# 1KB_I2C_EEPROM.net
KiCad netlist of a schematic drawn in Altium Designer
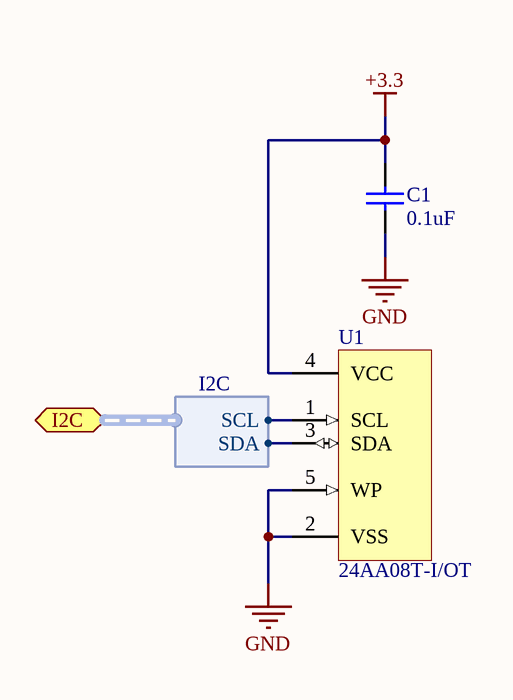
[diagram p0: 1KB I2C EEPROM.SchDoc]

(export (version "E")
  (design (tool "Eeschema 10.0.6"))
  (components
    (comp (ref "C1")
      (value "0.1uF")
      (footprint "C0603")
      (description "Capacitor")
      (fields (field (name "Comment") "Cap"))
      (libsource (lib "Miscellaneous Devices") (part "Cap"))
    )
    (comp (ref "U1")
      (value "24AA08T-I/OT")
      (footprint "24AA08T-I/OT")
      (description "MICROCHIP - 24AA08T-I/OT - EEPROM SERIAL 8KB, SMD, SOT-23-5")
      (libsource (lib "24AA08T-I_OT") (part "24AA08T-I/OT"))
    )
  )
  (nets
    (net (code "2") (name "+3.3") (class "Default")
      (node (ref "C1") (pin "1") (pinfunction "1_1") (pintype "passive"))
      (node (ref "U1") (pin "4") (pinfunction "VCC_4") (pintype "power_in"))
    )
    (net (code "3") (name "/SCL") (class "Default")
      (node (ref "U1") (pin "1") (pinfunction "SCL_1") (pintype "input"))
    )
    (net (code "4") (name "/SDA") (class "Default")
      (node (ref "U1") (pin "3") (pinfunction "SDA_3") (pintype "bidirectional"))
    )
    (net (code "6") (name "GND") (class "Default")
      (node (ref "C1") (pin "2") (pinfunction "2_2") (pintype "passive"))
      (node (ref "U1") (pin "2") (pinfunction "VSS_2") (pintype "power_in"))
      (node (ref "U1") (pin "5") (pinfunction "WP_5") (pintype "input"))
    )
  )
)
